# testsch.net
KiCad netlist of a schematic drawn in EAGLE
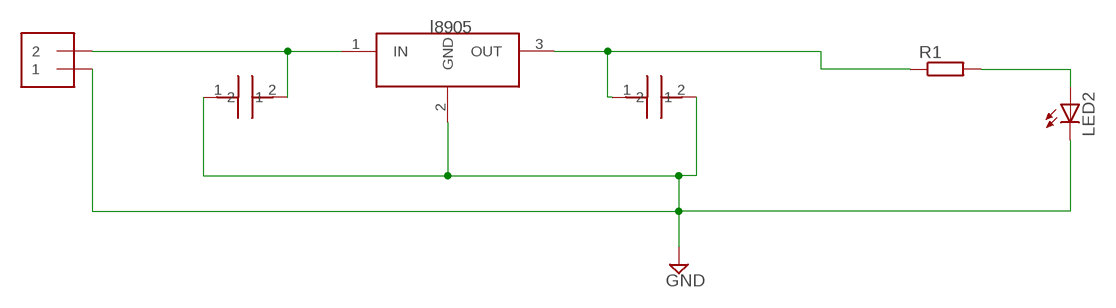
[diagram p0: schematic, sheet 1]

(export (version "E")
  (design (tool "Eeschema 10.0.6"))
  (components
    (comp (ref "J1")
      (value "1X2-3.5MM")
      (footprint "eagle-import:1X2-3.5MM")
      (libsource (lib "eagle-import") (part "1X2-3.5MM"))
    )
    (comp (ref "LED2")
      (value "LEDSMT1206")
      (footprint "eagle-import:1206")
      (libsource (lib "eagle-import") (part "LEDSMT1206"))
    )
    (comp (ref "R1")
      (value "R-EU_M1206")
      (footprint "eagle-import:M1206")
      (libsource (lib "eagle-import") (part "R-EU_M1206"))
    )
    (comp (ref "U$1")
      (value "L7805TESTA")
      (footprint "eagle-import:L7805")
      (libsource (lib "eagle-import") (part "L7805TESTA"))
    )
    (comp (ref "U$2")
      (value "0.33UF_CUSTOM")
      (footprint "eagle-import:C1206")
      (libsource (lib "eagle-import") (part "0.33UF_CUSTOM"))
    )
    (comp (ref "U$3")
      (value "0.33UF_CUSTOM")
      (footprint "eagle-import:C1206")
      (libsource (lib "eagle-import") (part "0.33UF_CUSTOM"))
    )
  )
  (nets
    (net (code "1") (name "GND") (class "Default")
      (node (ref "J1") (pin "1") (pinfunction "1_1") (pintype "passive"))
      (node (ref "LED2") (pin "C") (pinfunction "C_C") (pintype "passive"))
      (node (ref "U$1") (pin "2") (pinfunction "GND_2") (pintype "bidirectional"))
      (node (ref "U$2") (pin "1") (pinfunction "1_1") (pintype "bidirectional"))
      (node (ref "U$3") (pin "2") (pinfunction "2_2") (pintype "bidirectional"))
    )
    (net (code "2") (name "Net-(LED2-PadA)") (class "Default")
      (node (ref "LED2") (pin "A") (pinfunction "A_A") (pintype "passive"))
      (node (ref "R1") (pin "2") (pinfunction "2_2") (pintype "passive"))
    )
    (net (code "3") (name "Net-(U$1-IN)") (class "Default")
      (node (ref "J1") (pin "2") (pinfunction "2_2") (pintype "passive"))
      (node (ref "U$1") (pin "1") (pinfunction "IN_1") (pintype "bidirectional"))
      (node (ref "U$2") (pin "2") (pinfunction "2_2") (pintype "bidirectional"))
    )
    (net (code "4") (name "Net-(U$1-OUT)") (class "Default")
      (node (ref "R1") (pin "1") (pinfunction "1_1") (pintype "passive"))
      (node (ref "U$1") (pin "3") (pinfunction "OUT_3") (pintype "bidirectional"))
      (node (ref "U$3") (pin "1") (pinfunction "1_1") (pintype "bidirectional"))
    )
  )
)
